# DM1097_IMX378.net
KiCad netlist of a schematic drawn in Altium Designer
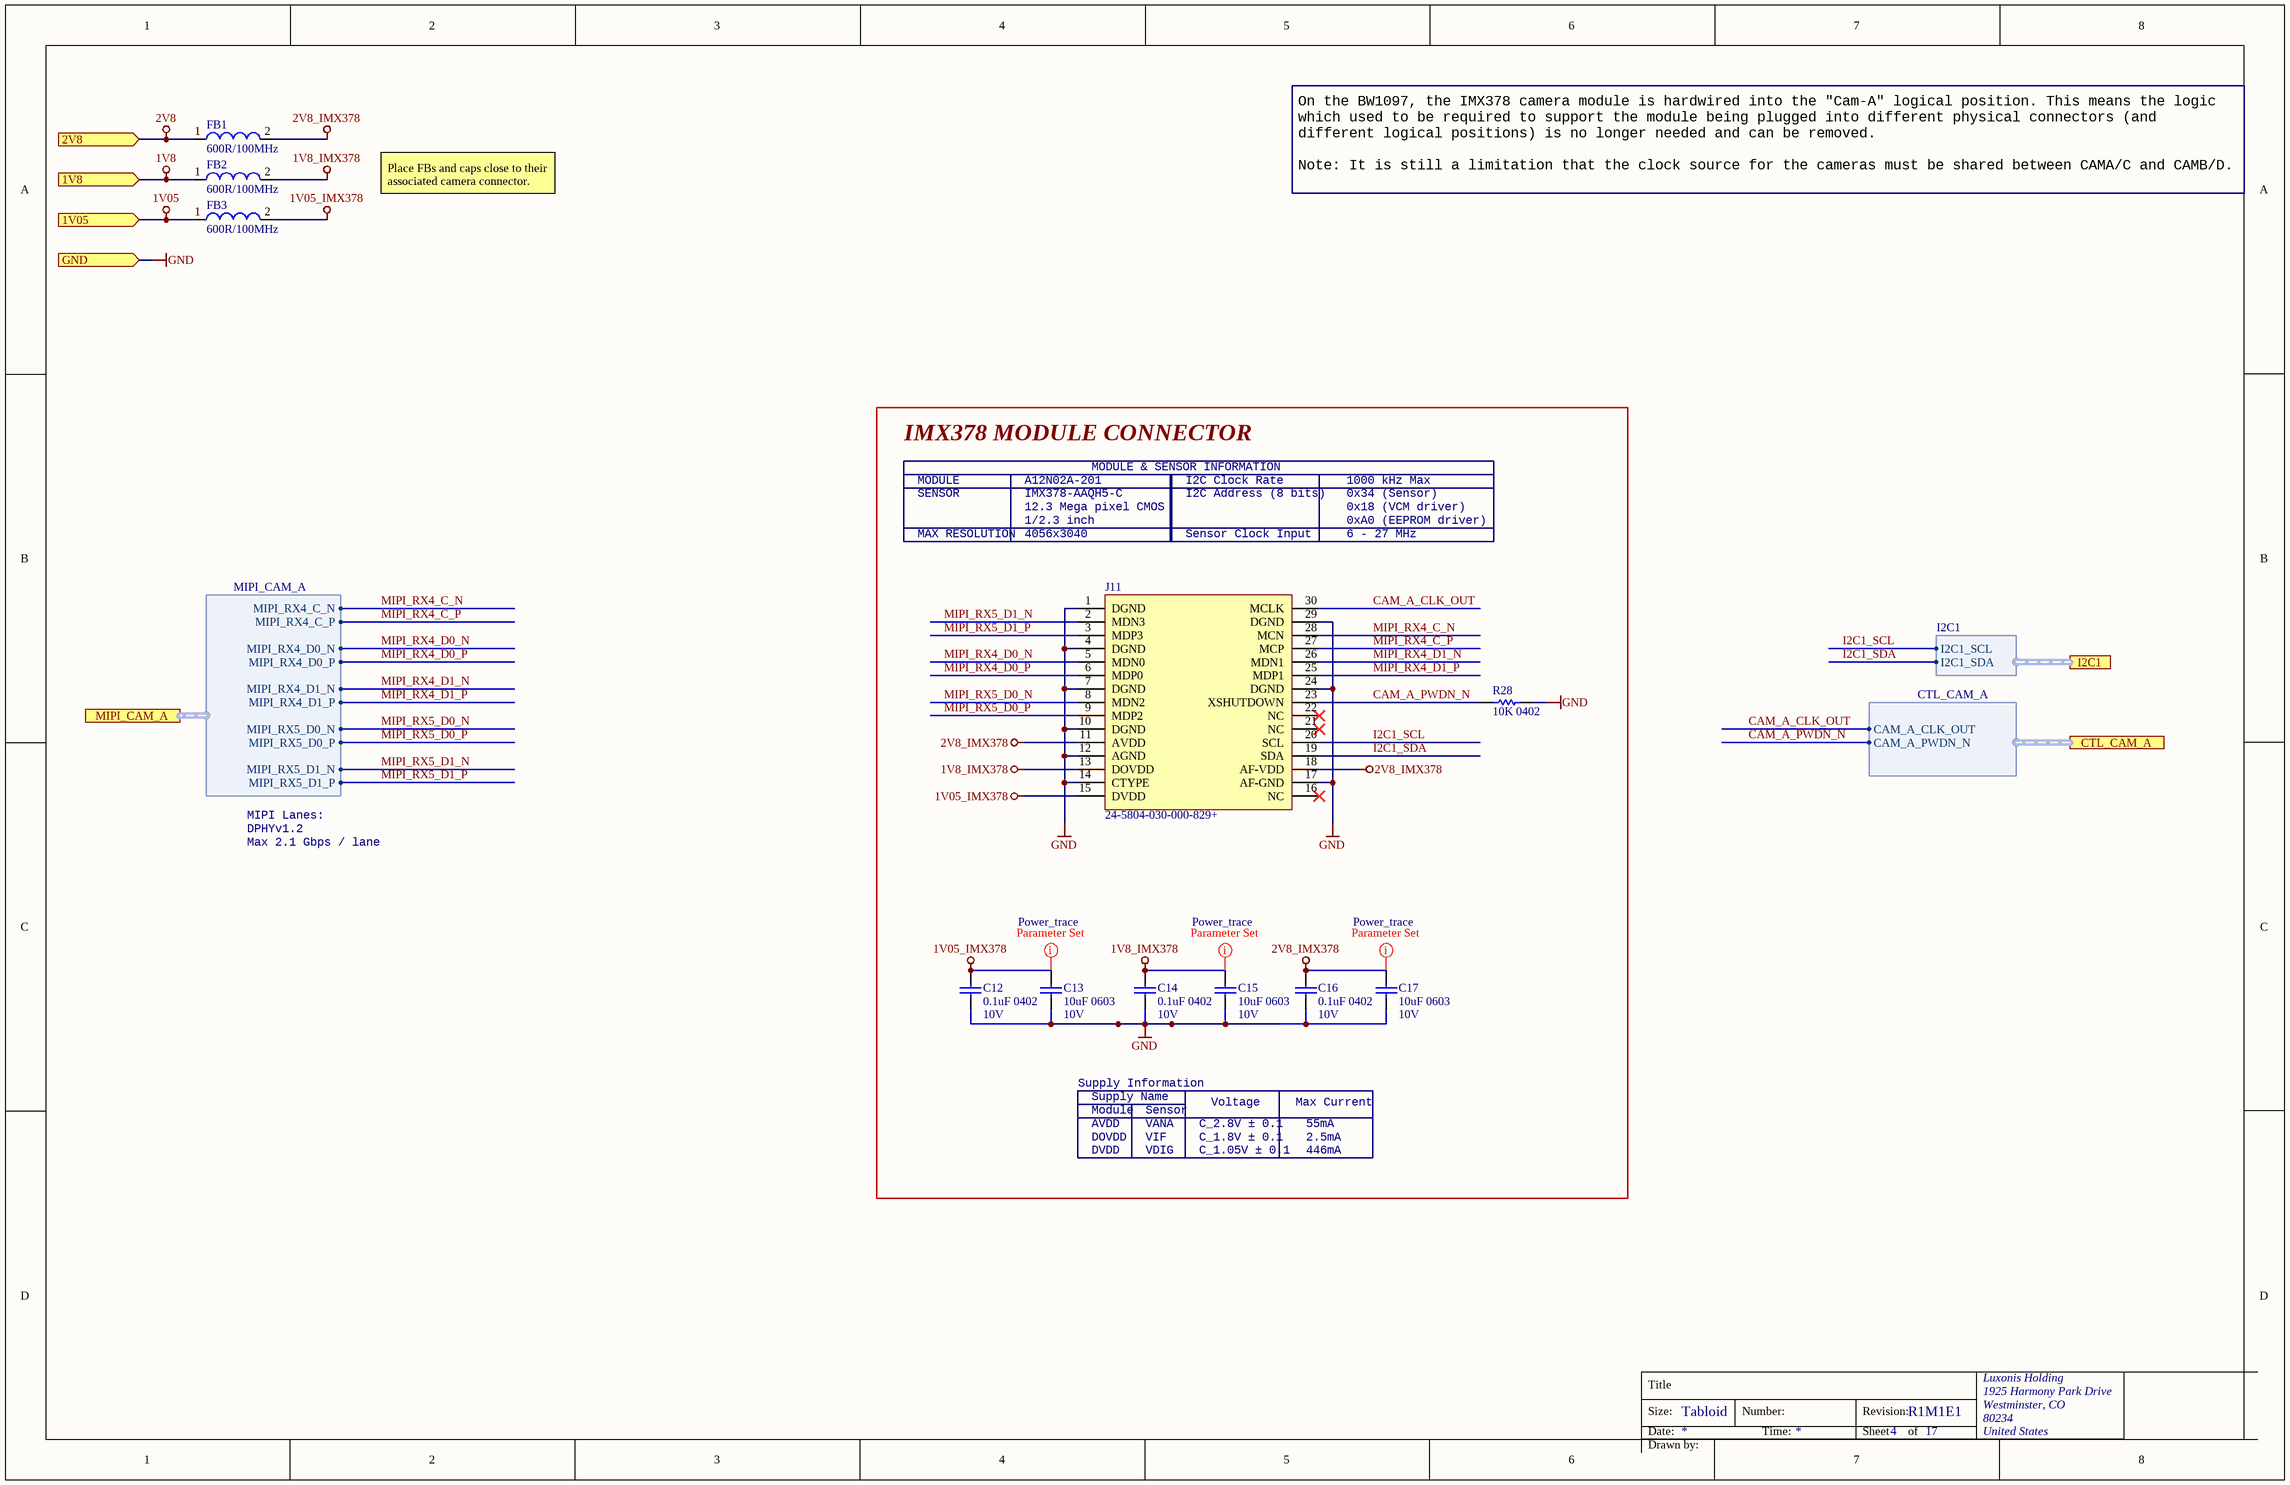
[diagram p0: DM1097_IMX378.SchDoc]

(export (version "E")
  (design (tool "Eeschema 10.0.6"))
  (components
    (comp (ref "C12")
      (value "0.1uF 0402")
      (footprint "CAP_Altium_Vault_Generic:CAPC0402(1005)70_N")
      (description "CAP CER 0.1UF 10V X7R 0402 5%")
      (fields (field (name "TOLERANCE") "5%") (field (name "VOLTAGE RATING") "10V"))
      (libsource (lib "LuxonisMaster") (part "GRM155R71A104JA01D"))
    )
    (comp (ref "C13")
      (value "10uF 0603")
      (footprint "CAP_Altium_Vault_Generic:CAPC0603(1608)100_N")
      (description "CAP CER 10UF 10V X5R 0603 20%")
      (fields (field (name "TOLERANCE") "20%") (field (name "VOLTAGE RATING") "10V"))
      (libsource (lib "LuxonisMaster") (part "GRM188R61A106ME69D"))
    )
    (comp (ref "C14")
      (value "0.1uF 0402")
      (footprint "CAP_Altium_Vault_Generic:CAPC0402(1005)70_N")
      (description "CAP CER 0.1UF 10V X7R 0402 5%")
      (fields (field (name "TOLERANCE") "5%") (field (name "VOLTAGE RATING") "10V"))
      (libsource (lib "LuxonisMaster") (part "GRM155R71A104JA01D"))
    )
    (comp (ref "C15")
      (value "10uF 0603")
      (footprint "CAP_Altium_Vault_Generic:CAPC0603(1608)100_N")
      (description "CAP CER 10UF 10V X5R 0603 20%")
      (fields (field (name "TOLERANCE") "20%") (field (name "VOLTAGE RATING") "10V"))
      (libsource (lib "LuxonisMaster") (part "GRM188R61A106ME69D"))
    )
    (comp (ref "C16")
      (value "0.1uF 0402")
      (footprint "CAP_Altium_Vault_Generic:CAPC0402(1005)70_N")
      (description "CAP CER 0.1UF 10V X7R 0402 5%")
      (fields (field (name "TOLERANCE") "5%") (field (name "VOLTAGE RATING") "10V"))
      (libsource (lib "LuxonisMaster") (part "GRM155R71A104JA01D"))
    )
    (comp (ref "C17")
      (value "10uF 0603")
      (footprint "CAP_Altium_Vault_Generic:CAPC0603(1608)100_N")
      (description "CAP CER 10UF 10V X5R 0603 20%")
      (fields (field (name "TOLERANCE") "20%") (field (name "VOLTAGE RATING") "10V"))
      (libsource (lib "LuxonisMaster") (part "GRM188R61A106ME69D"))
    )
    (comp (ref "FB1")
      (value "600R/100MHz")
      (footprint "LuxonisMaster:2508056017Y2")
      (description "FERRITE BEAD, 0.1OHM, 2A, 0805, 600R/100MHz")
      (fields (field (name "TOLERANCE") "25%"))
      (libsource (lib "LuxonisMaster") (part "2508056017Y2"))
    )
    (comp (ref "FB2")
      (value "600R/100MHz")
      (footprint "LuxonisMaster:2508056017Y2")
      (description "FERRITE BEAD, 0.1OHM, 2A, 0805, 600R/100MHz")
      (fields (field (name "TOLERANCE") "25%"))
      (libsource (lib "LuxonisMaster") (part "2508056017Y2"))
    )
    (comp (ref "FB3")
      (value "600R/100MHz")
      (footprint "LuxonisMaster:2508056017Y2")
      (description "FERRITE BEAD, 0.1OHM, 2A, 0805, 600R/100MHz")
      (fields (field (name "TOLERANCE") "25%"))
      (libsource (lib "LuxonisMaster") (part "2508056017Y2"))
    )
    (comp (ref "J11")
      (value "24-5804-030-000-829+")
      (footprint "LuxonisMaster:A12N02A-201_1.6mmbrd_MatedModule")
      (description "CONN Series 5804 board to board 0.4mm pitch 30 way connector")
      (libsource (lib "LuxonisMaster") (part "A12N02A-201_Connector"))
    )
    (comp (ref "R28")
      (value "10K 0402")
      (footprint "RES_Altium_Vault_Generic:RESC0402(1005)_N")
      (fields (field (name "TOLERANCE") "1%"))
      (libsource (lib "LuxonisMaster") (part "RC0402FR-1310KL"))
    )
  )
  (nets
    (net (code "4") (name "/CAM_A_CLK_OUT") (class "Default")
      (node (ref "J11") (pin "30") (pinfunction "MCLK_30") (pintype "passive"))
    )
    (net (code "5") (name "/CAM_A_PWDN_N") (class "Default")
      (node (ref "J11") (pin "23") (pinfunction "XSHUTDOWN_23") (pintype "passive"))
      (node (ref "R28") (pin "1") (pinfunction "1_1") (pintype "passive"))
    )
    (net (code "6") (name "/I2C1_SCL") (class "Default")
      (node (ref "J11") (pin "20") (pinfunction "SCL_20") (pintype "passive"))
    )
    (net (code "7") (name "/I2C1_SDA") (class "Default")
      (node (ref "J11") (pin "19") (pinfunction "SDA_19") (pintype "passive"))
    )
    (net (code "8") (name "/MIPI_RX4_C_N") (class "Default")
      (node (ref "J11") (pin "28") (pinfunction "MCN_28") (pintype "passive"))
    )
    (net (code "9") (name "/MIPI_RX4_C_P") (class "Default")
      (node (ref "J11") (pin "27") (pinfunction "MCP_27") (pintype "passive"))
    )
    (net (code "10") (name "/MIPI_RX4_D0_N") (class "Default")
      (node (ref "J11") (pin "5") (pinfunction "MDN0_5") (pintype "passive"))
    )
    (net (code "11") (name "/MIPI_RX4_D0_P") (class "Default")
      (node (ref "J11") (pin "6") (pinfunction "MDP0_6") (pintype "passive"))
    )
    (net (code "12") (name "/MIPI_RX4_D1_N") (class "Default")
      (node (ref "J11") (pin "26") (pinfunction "MDN1_26") (pintype "passive"))
    )
    (net (code "13") (name "/MIPI_RX4_D1_P") (class "Default")
      (node (ref "J11") (pin "25") (pinfunction "MDP1_25") (pintype "passive"))
    )
    (net (code "14") (name "/MIPI_RX5_D0_N") (class "Default")
      (node (ref "J11") (pin "8") (pinfunction "MDN2_8") (pintype "passive"))
    )
    (net (code "15") (name "/MIPI_RX5_D0_P") (class "Default")
      (node (ref "J11") (pin "9") (pinfunction "MDP2_9") (pintype "passive"))
    )
    (net (code "16") (name "/MIPI_RX5_D1_N") (class "Default")
      (node (ref "J11") (pin "2") (pinfunction "MDN3_2") (pintype "passive"))
    )
    (net (code "17") (name "/MIPI_RX5_D1_P") (class "Default")
      (node (ref "J11") (pin "3") (pinfunction "MDP3_3") (pintype "passive"))
    )
    (net (code "21") (name "1V05") (class "Default")
      (node (ref "FB3") (pin "1") (pinfunction "1_1") (pintype "passive"))
    )
    (net (code "22") (name "1V05_IMX378") (class "Default")
      (node (ref "C12") (pin "2") (pinfunction "2_2") (pintype "passive"))
      (node (ref "C13") (pin "2") (pinfunction "2_2") (pintype "passive"))
      (node (ref "FB3") (pin "2") (pinfunction "2_2") (pintype "passive"))
      (node (ref "J11") (pin "15") (pinfunction "DVDD_15") (pintype "passive"))
    )
    (net (code "23") (name "1V8") (class "Default")
      (node (ref "FB2") (pin "1") (pinfunction "1_1") (pintype "passive"))
    )
    (net (code "24") (name "1V8_IMX378") (class "Default")
      (node (ref "C14") (pin "2") (pinfunction "2_2") (pintype "passive"))
      (node (ref "C15") (pin "2") (pinfunction "2_2") (pintype "passive"))
      (node (ref "FB2") (pin "2") (pinfunction "2_2") (pintype "passive"))
      (node (ref "J11") (pin "13") (pinfunction "DOVDD_13") (pintype "passive"))
    )
    (net (code "25") (name "2V8") (class "Default")
      (node (ref "FB1") (pin "1") (pinfunction "1_1") (pintype "passive"))
    )
    (net (code "26") (name "2V8_IMX378") (class "Default")
      (node (ref "C16") (pin "2") (pinfunction "2_2") (pintype "passive"))
      (node (ref "C17") (pin "2") (pinfunction "2_2") (pintype "passive"))
      (node (ref "FB1") (pin "2") (pinfunction "2_2") (pintype "passive"))
      (node (ref "J11") (pin "11") (pinfunction "AVDD_11") (pintype "passive"))
      (node (ref "J11") (pin "18") (pinfunction "AF-VDD_18") (pintype "passive"))
    )
    (net (code "27") (name "GND") (class "Default")
      (node (ref "C12") (pin "1") (pinfunction "1_1") (pintype "passive"))
      (node (ref "C13") (pin "1") (pinfunction "1_1") (pintype "passive"))
      (node (ref "C14") (pin "1") (pinfunction "1_1") (pintype "passive"))
      (node (ref "C15") (pin "1") (pinfunction "1_1") (pintype "passive"))
      (node (ref "C16") (pin "1") (pinfunction "1_1") (pintype "passive"))
      (node (ref "C17") (pin "1") (pinfunction "1_1") (pintype "passive"))
      (node (ref "J11") (pin "1") (pinfunction "DGND_1") (pintype "passive"))
      (node (ref "J11") (pin "10") (pinfunction "DGND_10") (pintype "passive"))
      (node (ref "J11") (pin "12") (pinfunction "AGND_12") (pintype "passive"))
      (node (ref "J11") (pin "14") (pinfunction "CTYPE_14") (pintype "passive"))
      (node (ref "J11") (pin "17") (pinfunction "AF-GND_17") (pintype "passive"))
      (node (ref "J11") (pin "24") (pinfunction "DGND_24") (pintype "passive"))
      (node (ref "J11") (pin "29") (pinfunction "DGND_29") (pintype "passive"))
      (node (ref "J11") (pin "4") (pinfunction "DGND_4") (pintype "passive"))
      (node (ref "J11") (pin "7") (pinfunction "DGND_7") (pintype "passive"))
      (node (ref "R28") (pin "2") (pinfunction "2_2") (pintype "passive"))
    )
    (net (code "28") (name "unconnected-(J11-NC-Pad16)") (class "Default")
      (node (ref "J11") (pin "16") (pinfunction "NC_16") (pintype "passive+no_connect"))
    )
    (net (code "29") (name "unconnected-(J11-NC-Pad21)") (class "Default")
      (node (ref "J11") (pin "21") (pinfunction "NC_21") (pintype "passive+no_connect"))
    )
    (net (code "30") (name "unconnected-(J11-NC-Pad22)") (class "Default")
      (node (ref "J11") (pin "22") (pinfunction "NC_22") (pintype "passive+no_connect"))
    )
  )
)
